# Schematic.net
KiCad netlist of a schematic drawn in Altium Designer
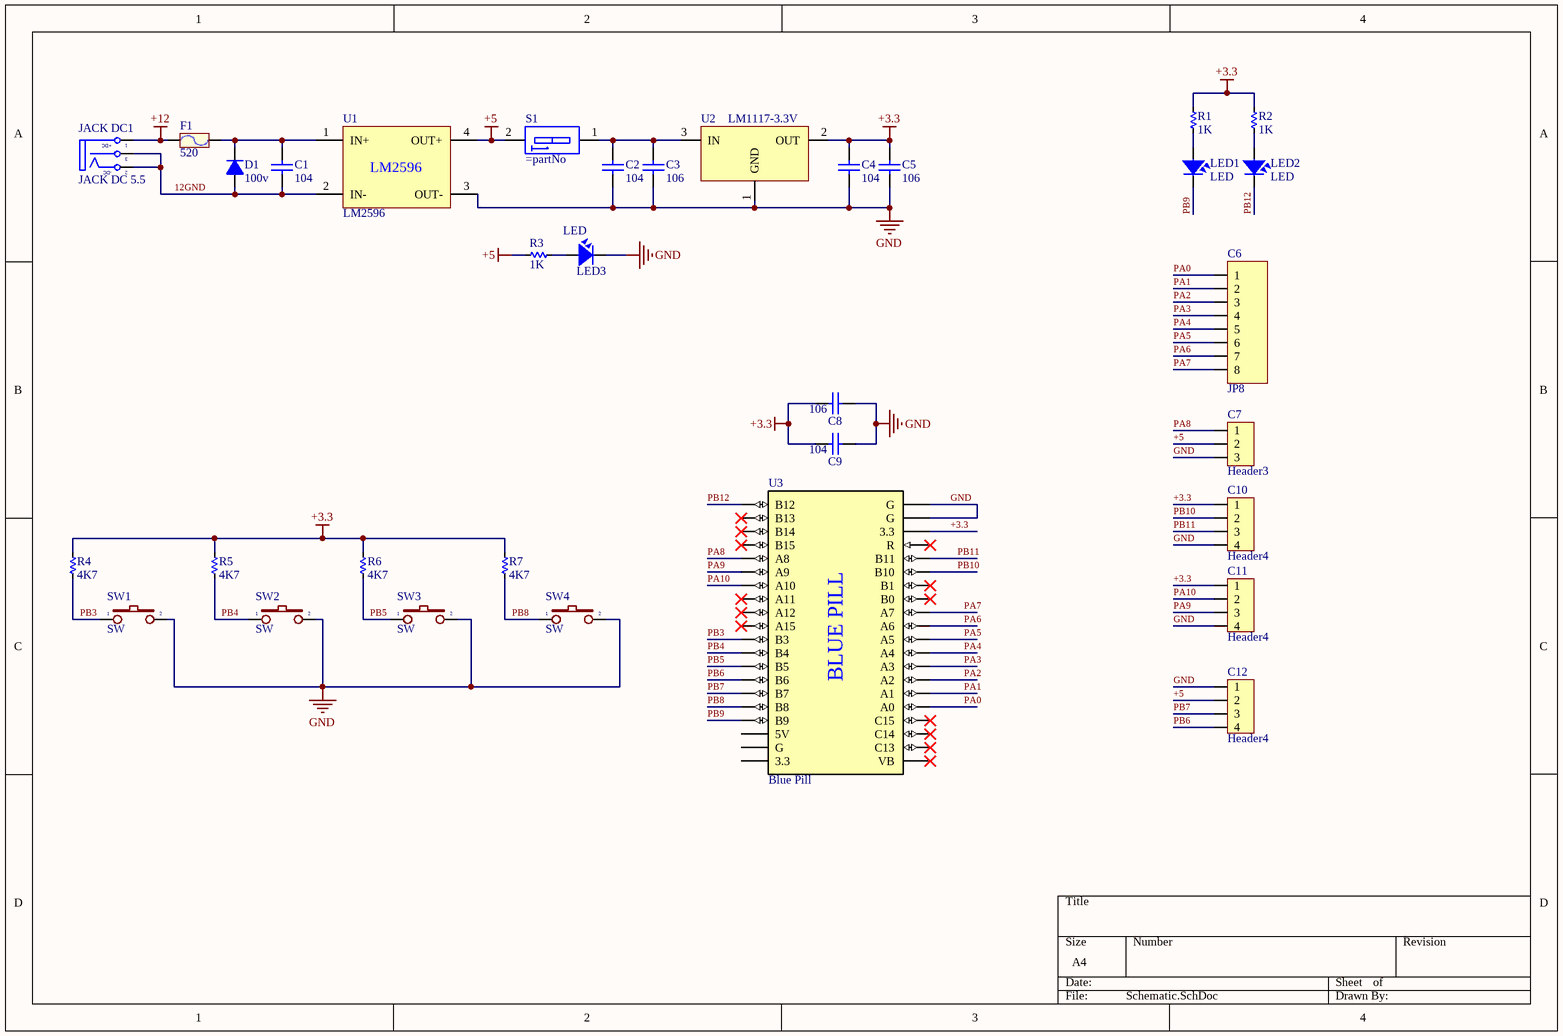
[diagram p0: Schematic.SchDoc]

(export (version "E")
  (design (tool "Eeschema 10.0.6"))
  (components
    (comp (ref "C1")
      (value "104")
      (footprint "tu gom")
      (description "Cắm")
      (libsource (lib "Altium_Lib_by_KhueNguyenCreator") (part "Tu gom 104 50V"))
    )
    (comp (ref "C2")
      (value "104")
      (footprint "tu gom")
      (description "Cắm")
      (libsource (lib "Altium_Lib_by_KhueNguyenCreator") (part "Tu gom 104 50V"))
    )
    (comp (ref "C3")
      (value "106")
      (footprint "tu gom")
      (description "Cắm")
      (libsource (lib "Altium_Lib_by_KhueNguyenCreator") (part "Tu gom 104 50V"))
    )
    (comp (ref "C4")
      (value "104")
      (footprint "tu gom")
      (description "Cắm")
      (libsource (lib "Altium_Lib_by_KhueNguyenCreator") (part "Tu gom 104 50V"))
    )
    (comp (ref "C5")
      (value "106")
      (footprint "tu gom")
      (description "Cắm")
      (libsource (lib "Altium_Lib_by_KhueNguyenCreator") (part "Tu gom 104 50V"))
    )
    (comp (ref "C6")
      (value "JP8")
      (footprint "JP8-D1T")
      (description "WR-PHD 2.54 mm Angled Socket Header")
      (fields
        (field (name "MANUFACTURER") "Würth Elektronik eiSos GmbH")
        (field (name "PARTNO") "613008143121")
        (field (name "CREATED BY") "Karrer Zheng")
      )
      (libsource (lib "TechMT.VN_Lib_Project v2") (part "JP8"))
    )
    (comp (ref "C7")
      (value "Header3")
      (footprint "Header3")
      (description "Header IDC, 3 x 1 Pin Vertical 2.54mm Pitch (Non-Boxed, Male)")
      (fields
        (field (name "MANUFACTURER") "Würth Elektronik eiSos GmbH")
        (field (name "PARTNO") "613002143121")
        (field (name "CREATED BY") "Karrer Zheng")
      )
      (libsource (lib "TechMT.VN_Lib_Project v2") (part "Header3"))
    )
    (comp (ref "C8")
      (value "106")
      (footprint "tu gom")
      (description "Cắm")
      (libsource (lib "Altium_Lib_by_KhueNguyenCreator") (part "Tu gom 104 50V"))
    )
    (comp (ref "C9")
      (value "104")
      (footprint "tu gom")
      (description "Cắm")
      (libsource (lib "Altium_Lib_by_KhueNguyenCreator") (part "Tu gom 104 50V"))
    )
    (comp (ref "C10")
      (value "Header4")
      (footprint "Header4")
      (description "Header IDC, 4 x 1 Pin Vertical 2.54mm Pitch (Non-Boxed, Male)")
      (fields
        (field (name "MANUFACTURER") "Würth Elektronik eiSos GmbH")
        (field (name "PARTNO") "613002143121")
        (field (name "CREATED BY") "Karrer Zheng")
      )
      (libsource (lib "TechMT.VN_Lib_Project v2") (part "Header4"))
    )
    (comp (ref "C11")
      (value "Header4")
      (footprint "Header4")
      (description "Header IDC, 4 x 1 Pin Vertical 2.54mm Pitch (Non-Boxed, Male)")
      (fields
        (field (name "MANUFACTURER") "Würth Elektronik eiSos GmbH")
        (field (name "PARTNO") "613002143121")
        (field (name "CREATED BY") "Karrer Zheng")
      )
      (libsource (lib "TechMT.VN_Lib_Project v2") (part "Header4"))
    )
    (comp (ref "C12")
      (value "Header4")
      (footprint "Header4")
      (description "Header IDC, 4 x 1 Pin Vertical 2.54mm Pitch (Non-Boxed, Male)")
      (fields
        (field (name "MANUFACTURER") "Würth Elektronik eiSos GmbH")
        (field (name "PARTNO") "613002143121")
        (field (name "CREATED BY") "Karrer Zheng")
      )
      (libsource (lib "TechMT.VN_Lib_Project v2") (part "Header4"))
    )
    (comp (ref "D1")
      (value "100v")
      (footprint "DIODE 1A")
      (description "Cắm")
      (libsource (lib "Altium_Lib_by_KhueNguyenCreator") (part "Diode 1N4007"))
    )
    (comp (ref "F1")
      (value "520")
      (footprint "De Cau Chi 520 630")
      (description "5x20mm")
      (libsource (lib "Altium_Lib_by_KhueNguyenCreator") (part "De Cau Chi 520 630"))
    )
    (comp (ref "JACK DC1")
      (value "JACK DC 5.5")
      (footprint "JACK DC 5.5")
      (libsource (lib "Altium_Lib_by_KhueNguyenCreator") (part "JACK DC 5.5"))
    )
    (comp (ref "LED1")
      (value "LED")
      (footprint "LED-3MM-YELLOW")
      (description "LED Single colour Green and Red")
      (libsource (lib "TechMT.VN_Lib_Project v2") (part "LED"))
    )
    (comp (ref "LED2")
      (value "LED")
      (footprint "LED-3MM-YELLOW")
      (description "LED Single colour Green and Red")
      (libsource (lib "TechMT.VN_Lib_Project v2") (part "LED"))
    )
    (comp (ref "LED3")
      (value "LED")
      (footprint "LED-3MM-YELLOW")
      (description "LED Single colour Green and Red")
      (libsource (lib "TechMT.VN_Lib_Project v2") (part "LED"))
    )
    (comp (ref "R1")
      (value "1K")
      (footprint "RES-1/4W")
      (description "Res")
      (fields
        (field (name "MANUFACTURER") "Generic Components")
        (field (name "PUBLISHER") "Altium Hobart Technology Centre")
      )
      (libsource (lib "TechMT.VN_Lib_Project v2") (part "Res"))
    )
    (comp (ref "R2")
      (value "1K")
      (footprint "RES-1/4W")
      (description "Res")
      (fields
        (field (name "MANUFACTURER") "Generic Components")
        (field (name "PUBLISHER") "Altium Hobart Technology Centre")
      )
      (libsource (lib "TechMT.VN_Lib_Project v2") (part "Res"))
    )
    (comp (ref "R3")
      (value "1K")
      (footprint "RES-1/4W")
      (description "Res")
      (fields
        (field (name "MANUFACTURER") "Generic Components")
        (field (name "PUBLISHER") "Altium Hobart Technology Centre")
      )
      (libsource (lib "TechMT.VN_Lib_Project v2") (part "Res"))
    )
    (comp (ref "R4")
      (value "4K7")
      (footprint "RES-1/4W")
      (description "Res")
      (fields
        (field (name "MANUFACTURER") "Generic Components")
        (field (name "PUBLISHER") "Altium Hobart Technology Centre")
      )
      (libsource (lib "TechMT.VN_Lib_Project v2") (part "Res"))
    )
    (comp (ref "R5")
      (value "4K7")
      (footprint "RES-1/4W")
      (description "Res")
      (fields
        (field (name "MANUFACTURER") "Generic Components")
        (field (name "PUBLISHER") "Altium Hobart Technology Centre")
      )
      (libsource (lib "TechMT.VN_Lib_Project v2") (part "Res"))
    )
    (comp (ref "R6")
      (value "4K7")
      (footprint "RES-1/4W")
      (description "Res")
      (fields
        (field (name "MANUFACTURER") "Generic Components")
        (field (name "PUBLISHER") "Altium Hobart Technology Centre")
      )
      (libsource (lib "TechMT.VN_Lib_Project v2") (part "Res"))
    )
    (comp (ref "R7")
      (value "4K7")
      (footprint "RES-1/4W")
      (description "Res")
      (fields
        (field (name "MANUFACTURER") "Generic Components")
        (field (name "PUBLISHER") "Altium Hobart Technology Centre")
      )
      (libsource (lib "TechMT.VN_Lib_Project v2") (part "Res"))
    )
    (comp (ref "S1")
      (value "~")
      (footprint "SW-DIP1")
      (description "WS-DITV 2.54 mm small compact THT flat actuator with top tape")
      (fields
        (field (name "MANUFACTURER") "Wurth Elektronik")
        (field (name "PART NO.") "418127160901")
        (field (name "CREATED BY") "Baojun Chen")
      )
      (libsource (lib "TechMT.VN_Lib_Project v2") (part "SWDIP1"))
    )
    (comp (ref "SW1")
      (value "SW")
      (footprint "SW2")
      (description "Switch button 2 pin")
      (libsource (lib "syhaunguyen") (part "SW2"))
    )
    (comp (ref "SW2")
      (value "SW")
      (footprint "SW2")
      (description "Switch button 2 pin")
      (libsource (lib "syhaunguyen") (part "SW2"))
    )
    (comp (ref "SW3")
      (value "SW")
      (footprint "SW2")
      (description "Switch button 2 pin")
      (libsource (lib "syhaunguyen") (part "SW2"))
    )
    (comp (ref "SW4")
      (value "SW")
      (footprint "SW2")
      (description "Switch button 2 pin")
      (libsource (lib "syhaunguyen") (part "SW2"))
    )
    (comp (ref "U1")
      (value "LM2596")
      (footprint "AZ_Lib:LM2596 Module")
      (description "DC - DC Buck")
      (libsource (lib "AZ_Lib") (part "LM2596 Module"))
    )
    (comp (ref "U2")
      (value "LM1117-3.3V")
      (footprint "TO220-123")
      (description "800mA Low-Dropout Linear Regulator")
      (fields (field (name "CREATOR") "Nguyen Ba Bien"))
      (libsource (lib "TechMT.VN_Lib_Project v2") (part "LM1117"))
    )
    (comp (ref "U3")
      (value "Blue Pill")
      (footprint "AZ_Lib:Blue Pill STM32F103")
      (description "Blue Pill STM32F103C8T6")
      (libsource (lib "AZ_Lib") (part "Blue Pill STM32F103"))
    )
  )
  (nets
    (net (code "1") (name "+3.3") (class "Default")
      (node (ref "C10") (pin "1") (pinfunction "1_1") (pintype "passive"))
      (node (ref "C11") (pin "1") (pinfunction "1_1") (pintype "passive"))
      (node (ref "C4") (pin "1") (pinfunction "1_1") (pintype "passive"))
      (node (ref "C5") (pin "1") (pinfunction "1_1") (pintype "passive"))
      (node (ref "C8") (pin "1") (pinfunction "1_1") (pintype "passive"))
      (node (ref "C9") (pin "1") (pinfunction "1_1") (pintype "passive"))
      (node (ref "R1") (pin "2") (pinfunction "2_2") (pintype "passive"))
      (node (ref "R2") (pin "2") (pinfunction "2_2") (pintype "passive"))
      (node (ref "R4") (pin "1") (pinfunction "1_1") (pintype "passive"))
      (node (ref "R5") (pin "1") (pinfunction "1_1") (pintype "passive"))
      (node (ref "R6") (pin "1") (pinfunction "1_1") (pintype "passive"))
      (node (ref "R7") (pin "1") (pinfunction "1_1") (pintype "passive"))
      (node (ref "U2") (pin "2") (pinfunction "OUT_2") (pintype "passive"))
      (node (ref "U3") (pin "38") (pinfunction "3.3_38") (pintype "power_in"))
    )
    (net (code "2") (name "+5") (class "Default")
      (node (ref "C12") (pin "2") (pinfunction "2_2") (pintype "passive"))
      (node (ref "C7") (pin "2") (pinfunction "2_2") (pintype "passive"))
      (node (ref "R3") (pin "2") (pinfunction "2_2") (pintype "passive"))
      (node (ref "S1") (pin "2") (pinfunction "2_2") (pintype "passive"))
      (node (ref "U1") (pin "4") (pinfunction "OUT+_4") (pintype "passive"))
    )
    (net (code "3") (name "+12") (class "Default")
      (node (ref "F1") (pin "1") (pinfunction "1_1") (pintype "passive"))
      (node (ref "JACK DC1") (pin "1") (pinfunction "T_1") (pintype "passive"))
    )
    (net (code "4") (name "/12GND") (class "Default")
      (node (ref "C1") (pin "2") (pinfunction "2_2") (pintype "passive"))
      (node (ref "D1") (pin "1") (pinfunction "A_1") (pintype "passive"))
      (node (ref "JACK DC1") (pin "2") (pinfunction "TN_2") (pintype "passive"))
      (node (ref "JACK DC1") (pin "3") (pinfunction "S_3") (pintype "power_in"))
      (node (ref "U1") (pin "2") (pinfunction "IN-_2") (pintype "passive"))
    )
    (net (code "5") (name "/PA0") (class "Default")
      (node (ref "C6") (pin "1") (pinfunction "1_1") (pintype "passive"))
      (node (ref "U3") (pin "25") (pinfunction "A0_25") (pintype "bidirectional"))
    )
    (net (code "6") (name "/PA1") (class "Default")
      (node (ref "C6") (pin "2") (pinfunction "2_2") (pintype "passive"))
      (node (ref "U3") (pin "26") (pinfunction "A1_26") (pintype "bidirectional"))
    )
    (net (code "7") (name "/PA2") (class "Default")
      (node (ref "C6") (pin "3") (pinfunction "3_3") (pintype "passive"))
      (node (ref "U3") (pin "27") (pinfunction "A2_27") (pintype "bidirectional"))
    )
    (net (code "8") (name "/PA3") (class "Default")
      (node (ref "C6") (pin "4") (pinfunction "4_4") (pintype "passive"))
      (node (ref "U3") (pin "28") (pinfunction "A3_28") (pintype "bidirectional"))
    )
    (net (code "9") (name "/PA4") (class "Default")
      (node (ref "C6") (pin "5") (pinfunction "5_5") (pintype "passive"))
      (node (ref "U3") (pin "29") (pinfunction "A4_29") (pintype "bidirectional"))
    )
    (net (code "10") (name "/PA5") (class "Default")
      (node (ref "C6") (pin "6") (pinfunction "6_6") (pintype "passive"))
      (node (ref "U3") (pin "30") (pinfunction "A5_30") (pintype "bidirectional"))
    )
    (net (code "11") (name "/PA6") (class "Default")
      (node (ref "C6") (pin "7") (pinfunction "7_7") (pintype "passive"))
      (node (ref "U3") (pin "31") (pinfunction "A6_31") (pintype "bidirectional"))
    )
    (net (code "12") (name "/PA7") (class "Default")
      (node (ref "C6") (pin "8") (pinfunction "8_8") (pintype "passive"))
      (node (ref "U3") (pin "32") (pinfunction "A7_32") (pintype "bidirectional"))
    )
    (net (code "13") (name "/PA8") (class "Default")
      (node (ref "C7") (pin "1") (pinfunction "1_1") (pintype "passive"))
      (node (ref "U3") (pin "5") (pinfunction "A8_5") (pintype "bidirectional"))
    )
    (net (code "14") (name "/PA9") (class "Default")
      (node (ref "C11") (pin "3") (pinfunction "3_3") (pintype "passive"))
      (node (ref "U3") (pin "6") (pinfunction "A9_6") (pintype "bidirectional"))
    )
    (net (code "15") (name "/PA10") (class "Default")
      (node (ref "C11") (pin "2") (pinfunction "2_2") (pintype "passive"))
      (node (ref "U3") (pin "7") (pinfunction "A10_7") (pintype "bidirectional"))
    )
    (net (code "16") (name "/PB3") (class "Default")
      (node (ref "R4") (pin "2") (pinfunction "2_2") (pintype "passive"))
      (node (ref "SW1") (pin "1") (pinfunction "1_1") (pintype "passive"))
      (node (ref "U3") (pin "11") (pinfunction "B3_11") (pintype "bidirectional"))
    )
    (net (code "17") (name "/PB4") (class "Default")
      (node (ref "R5") (pin "2") (pinfunction "2_2") (pintype "passive"))
      (node (ref "SW2") (pin "1") (pinfunction "1_1") (pintype "passive"))
      (node (ref "U3") (pin "12") (pinfunction "B4_12") (pintype "bidirectional"))
    )
    (net (code "18") (name "/PB5") (class "Default")
      (node (ref "R6") (pin "2") (pinfunction "2_2") (pintype "passive"))
      (node (ref "SW3") (pin "1") (pinfunction "1_1") (pintype "passive"))
      (node (ref "U3") (pin "13") (pinfunction "B5_13") (pintype "bidirectional"))
    )
    (net (code "19") (name "/PB6") (class "Default")
      (node (ref "C12") (pin "4") (pinfunction "4_4") (pintype "passive"))
      (node (ref "U3") (pin "14") (pinfunction "B6_14") (pintype "bidirectional"))
    )
    (net (code "20") (name "/PB7") (class "Default")
      (node (ref "C12") (pin "3") (pinfunction "3_3") (pintype "passive"))
      (node (ref "U3") (pin "15") (pinfunction "B7_15") (pintype "bidirectional"))
    )
    (net (code "21") (name "/PB8") (class "Default")
      (node (ref "R7") (pin "2") (pinfunction "2_2") (pintype "passive"))
      (node (ref "SW4") (pin "1") (pinfunction "1_1") (pintype "passive"))
      (node (ref "U3") (pin "16") (pinfunction "B8_16") (pintype "bidirectional"))
    )
    (net (code "22") (name "/PB9") (class "Default")
      (node (ref "LED1") (pin "2") (pinfunction "2_2") (pintype "passive"))
      (node (ref "U3") (pin "17") (pinfunction "B9_17") (pintype "bidirectional"))
    )
    (net (code "23") (name "/PB10") (class "Default")
      (node (ref "C10") (pin "2") (pinfunction "2_2") (pintype "passive"))
      (node (ref "U3") (pin "35") (pinfunction "B10_35") (pintype "bidirectional"))
    )
    (net (code "24") (name "/PB11") (class "Default")
      (node (ref "C10") (pin "3") (pinfunction "3_3") (pintype "passive"))
      (node (ref "U3") (pin "36") (pinfunction "B11_36") (pintype "bidirectional"))
    )
    (net (code "25") (name "/PB12") (class "Default")
      (node (ref "LED2") (pin "2") (pinfunction "2_2") (pintype "passive"))
      (node (ref "U3") (pin "1") (pinfunction "B12_1") (pintype "bidirectional"))
    )
    (net (code "26") (name "GND") (class "Default")
      (node (ref "C10") (pin "4") (pinfunction "4_4") (pintype "passive"))
      (node (ref "C11") (pin "4") (pinfunction "4_4") (pintype "passive"))
      (node (ref "C12") (pin "1") (pinfunction "1_1") (pintype "passive"))
      (node (ref "C2") (pin "2") (pinfunction "2_2") (pintype "passive"))
      (node (ref "C3") (pin "2") (pinfunction "2_2") (pintype "passive"))
      (node (ref "C4") (pin "2") (pinfunction "2_2") (pintype "passive"))
      (node (ref "C5") (pin "2") (pinfunction "2_2") (pintype "passive"))
      (node (ref "C7") (pin "3") (pinfunction "3_3") (pintype "passive"))
      (node (ref "C8") (pin "2") (pinfunction "2_2") (pintype "passive"))
      (node (ref "C9") (pin "2") (pinfunction "2_2") (pintype "passive"))
      (node (ref "LED3") (pin "2") (pinfunction "2_2") (pintype "passive"))
      (node (ref "SW1") (pin "2") (pinfunction "2_2") (pintype "passive"))
      (node (ref "SW2") (pin "2") (pinfunction "2_2") (pintype "passive"))
      (node (ref "SW3") (pin "2") (pinfunction "2_2") (pintype "passive"))
      (node (ref "SW4") (pin "2") (pinfunction "2_2") (pintype "passive"))
      (node (ref "U1") (pin "3") (pinfunction "OUT-_3") (pintype "passive"))
      (node (ref "U2") (pin "1") (pinfunction "GND_1") (pintype "passive"))
      (node (ref "U3") (pin "39") (pinfunction "G_39") (pintype "power_in"))
      (node (ref "U3") (pin "40") (pinfunction "G_40") (pintype "power_in"))
    )
    (net (code "27") (name "Net-(D1-K)") (class "Default")
      (node (ref "C1") (pin "1") (pinfunction "1_1") (pintype "passive"))
      (node (ref "D1") (pin "2") (pinfunction "K_2") (pintype "passive"))
      (node (ref "F1") (pin "2") (pinfunction "2_2") (pintype "passive"))
      (node (ref "U1") (pin "1") (pinfunction "IN+_1") (pintype "passive"))
    )
    (net (code "28") (name "Net-(LED1-Pad1)") (class "Default")
      (node (ref "LED1") (pin "1") (pinfunction "1_1") (pintype "passive"))
      (node (ref "R1") (pin "1") (pinfunction "1_1") (pintype "passive"))
    )
    (net (code "29") (name "Net-(LED2-Pad1)") (class "Default")
      (node (ref "LED2") (pin "1") (pinfunction "1_1") (pintype "passive"))
      (node (ref "R2") (pin "1") (pinfunction "1_1") (pintype "passive"))
    )
    (net (code "30") (name "Net-(LED3-Pad1)") (class "Default")
      (node (ref "LED3") (pin "1") (pinfunction "1_1") (pintype "passive"))
      (node (ref "R3") (pin "1") (pinfunction "1_1") (pintype "passive"))
    )
    (net (code "31") (name "Net-(U2-IN)") (class "Default")
      (node (ref "C2") (pin "1") (pinfunction "1_1") (pintype "passive"))
      (node (ref "C3") (pin "1") (pinfunction "1_1") (pintype "passive"))
      (node (ref "S1") (pin "1") (pinfunction "1_1") (pintype "passive"))
      (node (ref "U2") (pin "3") (pinfunction "IN_3") (pintype "passive"))
    )
    (net (code "32") (name "unconnected-(U3-3.3-Pad20)") (class "Default")
      (node (ref "U3") (pin "20") (pinfunction "3.3_20") (pintype "power_in"))
    )
    (net (code "33") (name "unconnected-(U3-5V-Pad18)") (class "Default")
      (node (ref "U3") (pin "18") (pinfunction "5V_18") (pintype "power_in"))
    )
    (net (code "34") (name "unconnected-(U3-A11-Pad8)") (class "Default")
      (node (ref "U3") (pin "8") (pinfunction "A11_8") (pintype "bidirectional+no_connect"))
    )
    (net (code "35") (name "unconnected-(U3-A12-Pad9)") (class "Default")
      (node (ref "U3") (pin "9") (pinfunction "A12_9") (pintype "bidirectional+no_connect"))
    )
    (net (code "36") (name "unconnected-(U3-A15-Pad10)") (class "Default")
      (node (ref "U3") (pin "10") (pinfunction "A15_10") (pintype "bidirectional+no_connect"))
    )
    (net (code "37") (name "unconnected-(U3-B0-Pad33)") (class "Default")
      (node (ref "U3") (pin "33") (pinfunction "B0_33") (pintype "bidirectional+no_connect"))
    )
    (net (code "38") (name "unconnected-(U3-B1-Pad34)") (class "Default")
      (node (ref "U3") (pin "34") (pinfunction "B1_34") (pintype "bidirectional+no_connect"))
    )
    (net (code "39") (name "unconnected-(U3-B13-Pad2)") (class "Default")
      (node (ref "U3") (pin "2") (pinfunction "B13_2") (pintype "bidirectional+no_connect"))
    )
    (net (code "40") (name "unconnected-(U3-B14-Pad3)") (class "Default")
      (node (ref "U3") (pin "3") (pinfunction "B14_3") (pintype "bidirectional+no_connect"))
    )
    (net (code "41") (name "unconnected-(U3-B15-Pad4)") (class "Default")
      (node (ref "U3") (pin "4") (pinfunction "B15_4") (pintype "bidirectional+no_connect"))
    )
    (net (code "42") (name "unconnected-(U3-C13-Pad22)") (class "Default")
      (node (ref "U3") (pin "22") (pinfunction "C13_22") (pintype "bidirectional+no_connect"))
    )
    (net (code "43") (name "unconnected-(U3-C14-Pad23)") (class "Default")
      (node (ref "U3") (pin "23") (pinfunction "C14_23") (pintype "bidirectional+no_connect"))
    )
    (net (code "44") (name "unconnected-(U3-C15-Pad24)") (class "Default")
      (node (ref "U3") (pin "24") (pinfunction "C15_24") (pintype "bidirectional+no_connect"))
    )
    (net (code "45") (name "unconnected-(U3-G-Pad19)") (class "Default")
      (node (ref "U3") (pin "19") (pinfunction "G_19") (pintype "power_in"))
    )
    (net (code "46") (name "unconnected-(U3-R-Pad37)") (class "Default")
      (node (ref "U3") (pin "37") (pinfunction "R_37") (pintype "input+no_connect"))
    )
    (net (code "47") (name "unconnected-(U3-VB-Pad21)") (class "Default")
      (node (ref "U3") (pin "21") (pinfunction "VB_21") (pintype "power_in+no_connect"))
    )
  )
)
